# tuggerTrackerV1.net
KiCad netlist of a schematic drawn in EAGLE
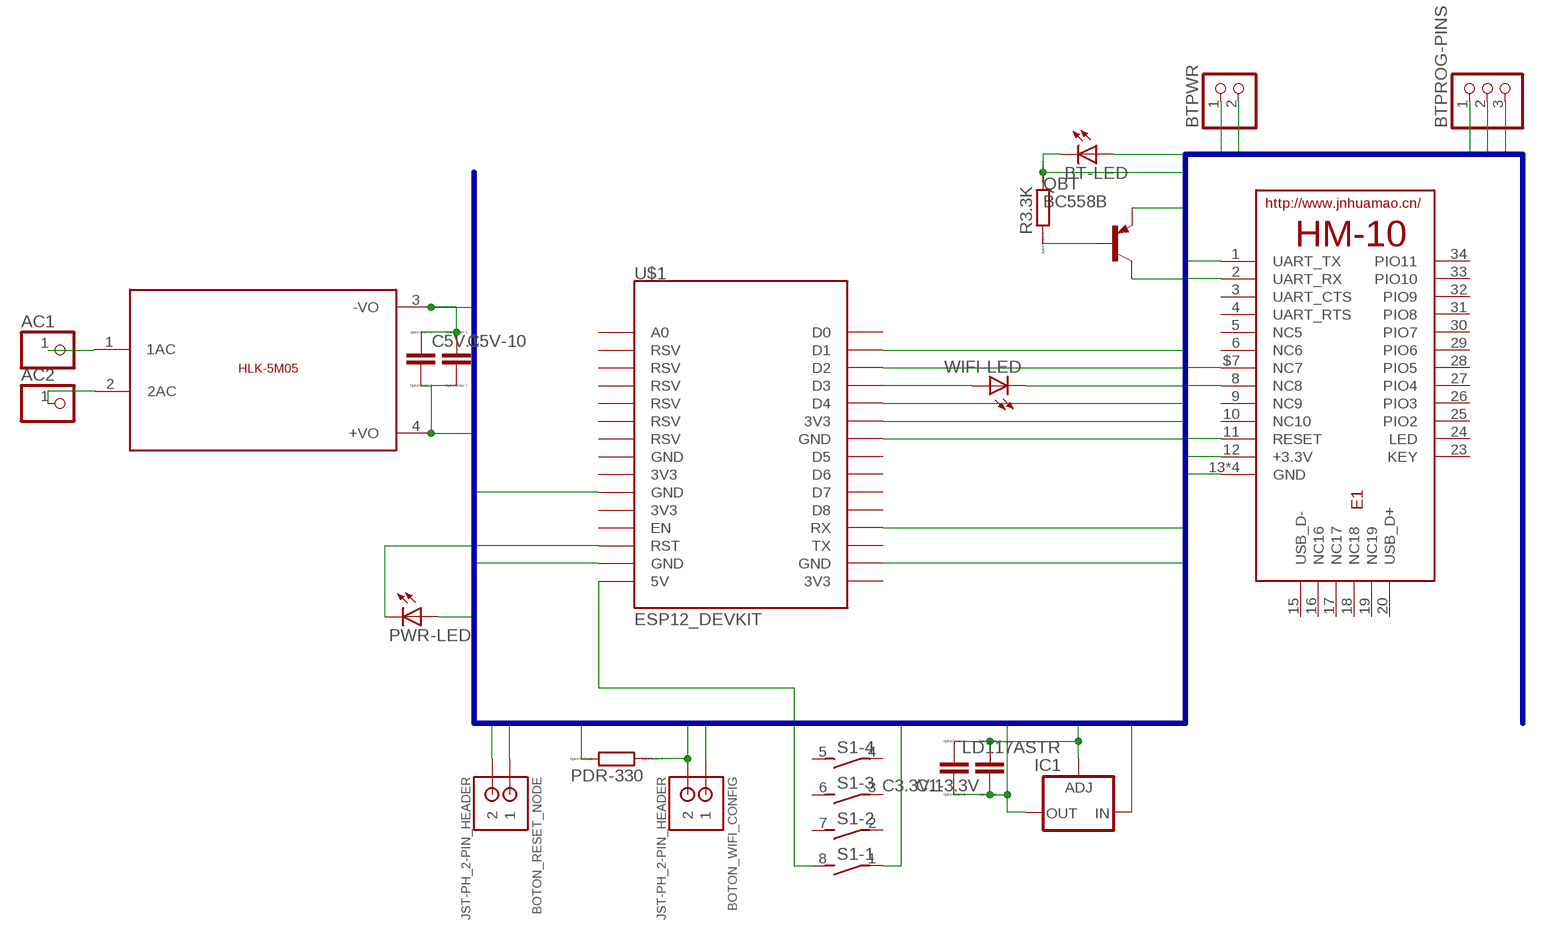
[diagram p0: schematic, sheet 1]

(export (version "E")
  (design (tool "Eeschema 10.0.6"))
  (components
    (comp (ref "AC1")
      (value "PINHD-1X1")
      (footprint "eagle-import:1X01")
      (libsource (lib "eagle-import") (part "PINHD-1X1"))
    )
    (comp (ref "AC2")
      (value "PINHD-1X1")
      (footprint "eagle-import:1X01")
      (libsource (lib "eagle-import") (part "PINHD-1X1"))
    )
    (comp (ref "BOTON_RESET_NODE")
      (value "JST-PH_2-PIN_HEADER")
      (footprint "eagle-import:JST_B2B-PH_HEADER")
      (libsource (lib "eagle-import") (part "JST-PH_2-PIN_HEADER"))
    )
    (comp (ref "BOTON_WIFI_CONFIG")
      (value "JST-PH_2-PIN_HEADER")
      (footprint "eagle-import:JST_B2B-PH_HEADER")
      (libsource (lib "eagle-import") (part "JST-PH_2-PIN_HEADER"))
    )
    (comp (ref "BT-LED")
      (value "LEDCHIPLED_1206")
      (footprint "eagle-import:CHIPLED_1206")
      (libsource (lib "eagle-import") (part "LEDCHIPLED_1206"))
    )
    (comp (ref "BTPROG-PINS")
      (value "PINHD-1X3")
      (footprint "eagle-import:1X03")
      (libsource (lib "eagle-import") (part "PINHD-1X3"))
    )
    (comp (ref "BTPWR")
      (value "PINHD-1X2")
      (footprint "eagle-import:1X02")
      (libsource (lib "eagle-import") (part "PINHD-1X2"))
    )
    (comp (ref "C1-3.3V")
      (value "CC0603")
      (footprint "eagle-import:C0603")
      (libsource (lib "eagle-import") (part "CC0603"))
    )
    (comp (ref "C3.3V.1")
      (value "CC0603")
      (footprint "eagle-import:C0603")
      (libsource (lib "eagle-import") (part "CC0603"))
    )
    (comp (ref "C5V-10")
      (value "CC0603")
      (footprint "eagle-import:C0603")
      (libsource (lib "eagle-import") (part "CC0603"))
    )
    (comp (ref "C5V.1")
      (value "CC0603")
      (footprint "eagle-import:C0603")
      (libsource (lib "eagle-import") (part "CC0603"))
    )
    (comp (ref "E1")
      (value "HM-10-BOARD")
      (footprint "eagle-import:26.9X13X2.2_BOARD")
      (libsource (lib "eagle-import") (part "HM-10-BOARD"))
    )
    (comp (ref "IC1")
      (value "LD117ASTR")
      (footprint "eagle-import:SOT223")
      (libsource (lib "eagle-import") (part "LD117A?STR"))
    )
    (comp (ref "PDR-330")
      (value "RR1206")
      (footprint "eagle-import:R1206")
      (libsource (lib "eagle-import") (part "RR1206"))
    )
    (comp (ref "PWR-LED")
      (value "LEDCHIPLED_1206")
      (footprint "eagle-import:CHIPLED_1206")
      (libsource (lib "eagle-import") (part "LEDCHIPLED_1206"))
    )
    (comp (ref "QBT")
      (value "BC558B")
      (footprint "eagle-import:TO92-EBC")
      (libsource (lib "eagle-import") (part "BC558B"))
    )
    (comp (ref "R3.3K")
      (value "RR1206")
      (footprint "eagle-import:R1206")
      (libsource (lib "eagle-import") (part "RR1206"))
    )
    (comp (ref "S1")
      (value "DIP04S")
      (footprint "eagle-import:DIP04S")
      (libsource (lib "eagle-import") (part "DIP04S"))
    )
    (comp (ref "U$1")
      (value "ESP12_DEVKIT")
      (footprint "eagle-import:ESP12_DEVKIT")
      (libsource (lib "eagle-import") (part "ESP12_DEVKIT"))
    )
    (comp (ref "U$2")
      (value "5VDC/5W")
      (footprint "eagle-import:HLK-5M05")
      (libsource (lib "eagle-import") (part "HLK-5M05"))
    )
    (comp (ref "WIFI-LED")
      (value "LEDCHIPLED_1206")
      (footprint "eagle-import:CHIPLED_1206")
      (libsource (lib "eagle-import") (part "LEDCHIPLED_1206"))
    )
  )
  (nets
    (net (code "1") (name "/BTPG1") (class "Default")
      (node (ref "BTPROG-PINS") (pin "1") (pinfunction "1_1") (pintype "passive"))
      (node (ref "E1") (pin "$7") (pinfunction "NC7_$7") (pintype "bidirectional"))
    )
    (net (code "2") (name "/BTPG2") (class "Default")
      (node (ref "BTPROG-PINS") (pin "2") (pinfunction "2_2") (pintype "passive"))
      (node (ref "E1") (pin "8") (pinfunction "NC8_8") (pintype "bidirectional"))
    )
    (net (code "3") (name "/BTRST") (class "Default")
      (node (ref "BTPROG-PINS") (pin "3") (pinfunction "3_3") (pintype "passive"))
      (node (ref "E1") (pin "11") (pinfunction "RESET_11") (pintype "bidirectional"))
    )
    (net (code "4") (name "/BTVCC") (class "Default")
      (node (ref "E1") (pin "12") (pinfunction "+3.3V_12") (pintype "bidirectional"))
      (node (ref "QBT") (pin "C") (pinfunction "C_C") (pintype "passive"))
    )
    (net (code "5") (name "/D1") (class "Default")
      (node (ref "BT-LED") (pin "C") (pinfunction "C_C") (pintype "passive"))
      (node (ref "R3.3K") (pin "2") (pinfunction "2_2") (pintype "passive"))
      (node (ref "U$1") (pin "D1") (pinfunction "D1_D1") (pintype "bidirectional"))
    )
    (net (code "6") (name "/D2") (class "Default")
      (node (ref "BOTON_WIFI_CONFIG") (pin "P2") (pinfunction "2_P2") (pintype "bidirectional"))
      (node (ref "PDR-330") (pin "1") (pinfunction "1_1") (pintype "passive"))
      (node (ref "U$1") (pin "D2") (pinfunction "D2_D2") (pintype "bidirectional"))
    )
    (net (code "7") (name "/GND") (class "Default")
      (node (ref "BOTON_RESET_NODE") (pin "P2") (pinfunction "2_P2") (pintype "bidirectional"))
      (node (ref "BTPWR") (pin "1") (pinfunction "1_1") (pintype "passive"))
      (node (ref "C1-3.3V") (pin "2") (pinfunction "2_2") (pintype "passive"))
      (node (ref "C3.3V.1") (pin "2") (pinfunction "2_2") (pintype "passive"))
      (node (ref "C5V-10") (pin "1") (pinfunction "1_1") (pintype "passive"))
      (node (ref "C5V.1") (pin "1") (pinfunction "1_1") (pintype "passive"))
      (node (ref "E1") (pin "13") (pinfunction "GND_13") (pintype "bidirectional"))
      (node (ref "E1") (pin "14") (pinfunction "GND_14") (pintype "bidirectional"))
      (node (ref "E1") (pin "21") (pinfunction "GND_21") (pintype "bidirectional"))
      (node (ref "E1") (pin "22") (pinfunction "GND_22") (pintype "bidirectional"))
      (node (ref "IC1") (pin "1") (pinfunction "ADJ_1") (pintype "input"))
      (node (ref "PDR-330") (pin "2") (pinfunction "2_2") (pintype "passive"))
      (node (ref "PWR-LED") (pin "C") (pinfunction "C_C") (pintype "passive"))
      (node (ref "U$1") (pin "GND@0") (pinfunction "GND_GND@0") (pintype "bidirectional"))
      (node (ref "U$1") (pin "GND@1") (pinfunction "GND_GND@1") (pintype "bidirectional"))
      (node (ref "U$1") (pin "GND@2") (pinfunction "GND_GND@2") (pintype "bidirectional"))
      (node (ref "U$1") (pin "GND@3") (pinfunction "GND_GND@3") (pintype "bidirectional"))
      (node (ref "U$2") (pin "3") (pinfunction "-VO_3") (pintype "bidirectional"))
      (node (ref "WIFI-LED") (pin "C") (pinfunction "C_C") (pintype "passive"))
    )
    (net (code "8") (name "/NODRST") (class "Default")
      (node (ref "BOTON_RESET_NODE") (pin "P1") (pinfunction "1_P1") (pintype "bidirectional"))
      (node (ref "U$1") (pin "RST") (pinfunction "RST_RST") (pintype "bidirectional"))
    )
    (net (code "9") (name "/NRXBTX") (class "Default")
      (node (ref "E1") (pin "1") (pinfunction "UART_TX_1") (pintype "bidirectional"))
      (node (ref "U$1") (pin "RX") (pinfunction "RX_RX") (pintype "bidirectional"))
    )
    (net (code "10") (name "/NTXBRX") (class "Default")
      (node (ref "E1") (pin "2") (pinfunction "UART_RX_2") (pintype "bidirectional"))
      (node (ref "U$1") (pin "D4") (pinfunction "D4_D4") (pintype "bidirectional"))
    )
    (net (code "11") (name "/V3NODE") (class "Default")
      (node (ref "BOTON_WIFI_CONFIG") (pin "P1") (pinfunction "1_P1") (pintype "bidirectional"))
      (node (ref "BT-LED") (pin "A") (pinfunction "A_A") (pintype "passive"))
      (node (ref "PWR-LED") (pin "A") (pinfunction "A_A") (pintype "passive"))
      (node (ref "U$1") (pin "3V3@1") (pinfunction "3V3_3V3@1") (pintype "bidirectional"))
    )
    (net (code "12") (name "/V3REG") (class "Default")
      (node (ref "C1-3.3V") (pin "1") (pinfunction "1_1") (pintype "passive"))
      (node (ref "C3.3V.1") (pin "1") (pinfunction "1_1") (pintype "passive"))
      (node (ref "IC1") (pin "4") (pinfunction "OUT_4") (pintype "passive"))
      (node (ref "QBT") (pin "E") (pinfunction "E_E") (pintype "passive"))
    )
    (net (code "13") (name "/VIN") (class "Default")
      (node (ref "BTPWR") (pin "2") (pinfunction "2_2") (pintype "passive"))
      (node (ref "C5V-10") (pin "2") (pinfunction "2_2") (pintype "passive"))
      (node (ref "C5V.1") (pin "2") (pinfunction "2_2") (pintype "passive"))
      (node (ref "IC1") (pin "3") (pinfunction "IN_3") (pintype "input"))
      (node (ref "S1") (pin "1") (pinfunction "1_1") (pintype "passive"))
      (node (ref "U$2") (pin "4") (pinfunction "+VO_4") (pintype "bidirectional"))
    )
    (net (code "14") (name "Net-(QBT-PadB)") (class "Default")
      (node (ref "QBT") (pin "B") (pinfunction "B_B") (pintype "passive"))
      (node (ref "R3.3K") (pin "1") (pinfunction "1_1") (pintype "passive"))
    )
    (net (code "15") (name "Net-(S1A-2)") (class "Default")
      (node (ref "S1") (pin "8") (pinfunction "2_8") (pintype "passive"))
      (node (ref "U$1") (pin "5V") (pinfunction "5V_5V") (pintype "bidirectional"))
    )
    (net (code "16") (name "Net-(U$1-PadD3)") (class "Default")
      (node (ref "U$1") (pin "D3") (pinfunction "D3_D3") (pintype "bidirectional"))
      (node (ref "WIFI-LED") (pin "A") (pinfunction "A_A") (pintype "passive"))
    )
    (net (code "17") (name "Net-(U$2-1AC)") (class "Default")
      (node (ref "AC1") (pin "1") (pinfunction "1_1") (pintype "passive"))
      (node (ref "U$2") (pin "1") (pinfunction "1AC_1") (pintype "bidirectional"))
    )
    (net (code "18") (name "Net-(U$2-2AC)") (class "Default")
      (node (ref "AC2") (pin "1") (pinfunction "1_1") (pintype "passive"))
      (node (ref "U$2") (pin "2") (pinfunction "2AC_2") (pintype "bidirectional"))
    )
    (net (code "19") (name "unconnected-(E1-KEY-Pad23)") (class "Default")
      (node (ref "E1") (pin "23") (pinfunction "KEY_23") (pintype "bidirectional"))
    )
    (net (code "20") (name "unconnected-(E1-LED-Pad24)") (class "Default")
      (node (ref "E1") (pin "24") (pinfunction "LED_24") (pintype "bidirectional"))
    )
    (net (code "21") (name "unconnected-(E1-NC5-Pad5)") (class "Default")
      (node (ref "E1") (pin "5") (pinfunction "NC5_5") (pintype "bidirectional"))
    )
    (net (code "22") (name "unconnected-(E1-NC6-Pad6)") (class "Default")
      (node (ref "E1") (pin "6") (pinfunction "NC6_6") (pintype "bidirectional"))
    )
    (net (code "23") (name "unconnected-(E1-NC9-Pad9)") (class "Default")
      (node (ref "E1") (pin "9") (pinfunction "NC9_9") (pintype "bidirectional"))
    )
    (net (code "24") (name "unconnected-(E1-NC10-Pad10)") (class "Default")
      (node (ref "E1") (pin "10") (pinfunction "NC10_10") (pintype "bidirectional"))
    )
    (net (code "25") (name "unconnected-(E1-NC16-Pad16)") (class "Default")
      (node (ref "E1") (pin "16") (pinfunction "NC16_16") (pintype "bidirectional"))
    )
    (net (code "26") (name "unconnected-(E1-NC17-Pad17)") (class "Default")
      (node (ref "E1") (pin "17") (pinfunction "NC17_17") (pintype "bidirectional"))
    )
    (net (code "27") (name "unconnected-(E1-NC18-Pad18)") (class "Default")
      (node (ref "E1") (pin "18") (pinfunction "NC18_18") (pintype "bidirectional"))
    )
    (net (code "28") (name "unconnected-(E1-NC19-Pad19)") (class "Default")
      (node (ref "E1") (pin "19") (pinfunction "NC19_19") (pintype "bidirectional"))
    )
    (net (code "29") (name "unconnected-(E1-PIO2-Pad25)") (class "Default")
      (node (ref "E1") (pin "25") (pinfunction "PIO2_25") (pintype "bidirectional"))
    )
    (net (code "30") (name "unconnected-(E1-PIO3-Pad26)") (class "Default")
      (node (ref "E1") (pin "26") (pinfunction "PIO3_26") (pintype "bidirectional"))
    )
    (net (code "31") (name "unconnected-(E1-PIO4-Pad27)") (class "Default")
      (node (ref "E1") (pin "27") (pinfunction "PIO4_27") (pintype "bidirectional"))
    )
    (net (code "32") (name "unconnected-(E1-PIO5-Pad28)") (class "Default")
      (node (ref "E1") (pin "28") (pinfunction "PIO5_28") (pintype "bidirectional"))
    )
    (net (code "33") (name "unconnected-(E1-PIO6-Pad29)") (class "Default")
      (node (ref "E1") (pin "29") (pinfunction "PIO6_29") (pintype "bidirectional"))
    )
    (net (code "34") (name "unconnected-(E1-PIO7-Pad30)") (class "Default")
      (node (ref "E1") (pin "30") (pinfunction "PIO7_30") (pintype "bidirectional"))
    )
    (net (code "35") (name "unconnected-(E1-PIO8-Pad31)") (class "Default")
      (node (ref "E1") (pin "31") (pinfunction "PIO8_31") (pintype "bidirectional"))
    )
    (net (code "36") (name "unconnected-(E1-PIO9-Pad32)") (class "Default")
      (node (ref "E1") (pin "32") (pinfunction "PIO9_32") (pintype "bidirectional"))
    )
    (net (code "37") (name "unconnected-(E1-PIO10-Pad33)") (class "Default")
      (node (ref "E1") (pin "33") (pinfunction "PIO10_33") (pintype "bidirectional"))
    )
    (net (code "38") (name "unconnected-(E1-PIO11-Pad34)") (class "Default")
      (node (ref "E1") (pin "34") (pinfunction "PIO11_34") (pintype "bidirectional"))
    )
    (net (code "39") (name "unconnected-(E1-UART_CTS-Pad3)") (class "Default")
      (node (ref "E1") (pin "3") (pinfunction "UART_CTS_3") (pintype "bidirectional"))
    )
    (net (code "40") (name "unconnected-(E1-UART_RTS-Pad4)") (class "Default")
      (node (ref "E1") (pin "4") (pinfunction "UART_RTS_4") (pintype "bidirectional"))
    )
    (net (code "41") (name "unconnected-(E1-USB_D+-Pad20)") (class "Default")
      (node (ref "E1") (pin "20") (pinfunction "USB_D+_20") (pintype "bidirectional"))
    )
    (net (code "42") (name "unconnected-(E1-USB_D--Pad15)") (class "Default")
      (node (ref "E1") (pin "15") (pinfunction "USB_D-_15") (pintype "bidirectional"))
    )
    (net (code "43") (name "unconnected-(S1B-1-Pad2)") (class "Default")
      (node (ref "S1") (pin "2") (pinfunction "1_2") (pintype "passive"))
    )
    (net (code "44") (name "unconnected-(S1B-2-Pad7)") (class "Default")
      (node (ref "S1") (pin "7") (pinfunction "2_7") (pintype "passive"))
    )
    (net (code "45") (name "unconnected-(S1C-1-Pad3)") (class "Default")
      (node (ref "S1") (pin "3") (pinfunction "1_3") (pintype "passive"))
    )
    (net (code "46") (name "unconnected-(S1C-2-Pad6)") (class "Default")
      (node (ref "S1") (pin "6") (pinfunction "2_6") (pintype "passive"))
    )
    (net (code "47") (name "unconnected-(S1D-1-Pad4)") (class "Default")
      (node (ref "S1") (pin "4") (pinfunction "1_4") (pintype "passive"))
    )
    (net (code "48") (name "unconnected-(S1D-2-Pad5)") (class "Default")
      (node (ref "S1") (pin "5") (pinfunction "2_5") (pintype "passive"))
    )
    (net (code "49") (name "unconnected-(U$1-3V3-Pad3V3@0)") (class "Default")
      (node (ref "U$1") (pin "3V3@0") (pinfunction "3V3_3V3@0") (pintype "bidirectional"))
    )
    (net (code "50") (name "unconnected-(U$1-3V3-Pad3V3@2)") (class "Default")
      (node (ref "U$1") (pin "3V3@2") (pinfunction "3V3_3V3@2") (pintype "bidirectional"))
    )
    (net (code "51") (name "unconnected-(U$1-3V3-Pad3V3@3)") (class "Default")
      (node (ref "U$1") (pin "3V3@3") (pinfunction "3V3_3V3@3") (pintype "bidirectional"))
    )
    (net (code "52") (name "unconnected-(U$1-GND-PadGND@4)") (class "Default")
      (node (ref "U$1") (pin "GND@4") (pinfunction "GND_GND@4") (pintype "bidirectional"))
    )
    (net (code "53") (name "unconnected-(U$1-PadA0)") (class "Default")
      (node (ref "U$1") (pin "A0") (pinfunction "A0_A0") (pintype "bidirectional"))
    )
    (net (code "54") (name "unconnected-(U$1-PadD0)") (class "Default")
      (node (ref "U$1") (pin "D0") (pinfunction "D0_D0") (pintype "bidirectional"))
    )
    (net (code "55") (name "unconnected-(U$1-PadD5)") (class "Default")
      (node (ref "U$1") (pin "D5") (pinfunction "D5_D5") (pintype "bidirectional"))
    )
    (net (code "56") (name "unconnected-(U$1-PadD6)") (class "Default")
      (node (ref "U$1") (pin "D6") (pinfunction "D6_D6") (pintype "bidirectional"))
    )
    (net (code "57") (name "unconnected-(U$1-PadD7)") (class "Default")
      (node (ref "U$1") (pin "D7") (pinfunction "D7_D7") (pintype "bidirectional"))
    )
    (net (code "58") (name "unconnected-(U$1-PadD8)") (class "Default")
      (node (ref "U$1") (pin "D8") (pinfunction "D8_D8") (pintype "bidirectional"))
    )
    (net (code "59") (name "unconnected-(U$1-PadEN)") (class "Default")
      (node (ref "U$1") (pin "EN") (pinfunction "EN_EN") (pintype "bidirectional"))
    )
    (net (code "60") (name "unconnected-(U$1-PadTX)") (class "Default")
      (node (ref "U$1") (pin "TX") (pinfunction "TX_TX") (pintype "bidirectional"))
    )
    (net (code "61") (name "unconnected-(U$1-RSV-PadRSV@0)") (class "Default")
      (node (ref "U$1") (pin "RSV@0") (pinfunction "RSV_RSV@0") (pintype "bidirectional"))
    )
    (net (code "62") (name "unconnected-(U$1-RSV-PadRSV@1)") (class "Default")
      (node (ref "U$1") (pin "RSV@1") (pinfunction "RSV_RSV@1") (pintype "bidirectional"))
    )
    (net (code "63") (name "unconnected-(U$1-RSV-PadRSV@2)") (class "Default")
      (node (ref "U$1") (pin "RSV@2") (pinfunction "RSV_RSV@2") (pintype "bidirectional"))
    )
    (net (code "64") (name "unconnected-(U$1-RSV-PadRSV@3)") (class "Default")
      (node (ref "U$1") (pin "RSV@3") (pinfunction "RSV_RSV@3") (pintype "bidirectional"))
    )
    (net (code "65") (name "unconnected-(U$1-RSV-PadRSV@4)") (class "Default")
      (node (ref "U$1") (pin "RSV@4") (pinfunction "RSV_RSV@4") (pintype "bidirectional"))
    )
    (net (code "66") (name "unconnected-(U$1-RSV-PadRSV@5)") (class "Default")
      (node (ref "U$1") (pin "RSV@5") (pinfunction "RSV_RSV@5") (pintype "bidirectional"))
    )
  )
)
